# Rudder_-_Prototype_2.net
KiCad netlist of a schematic drawn in EAGLE
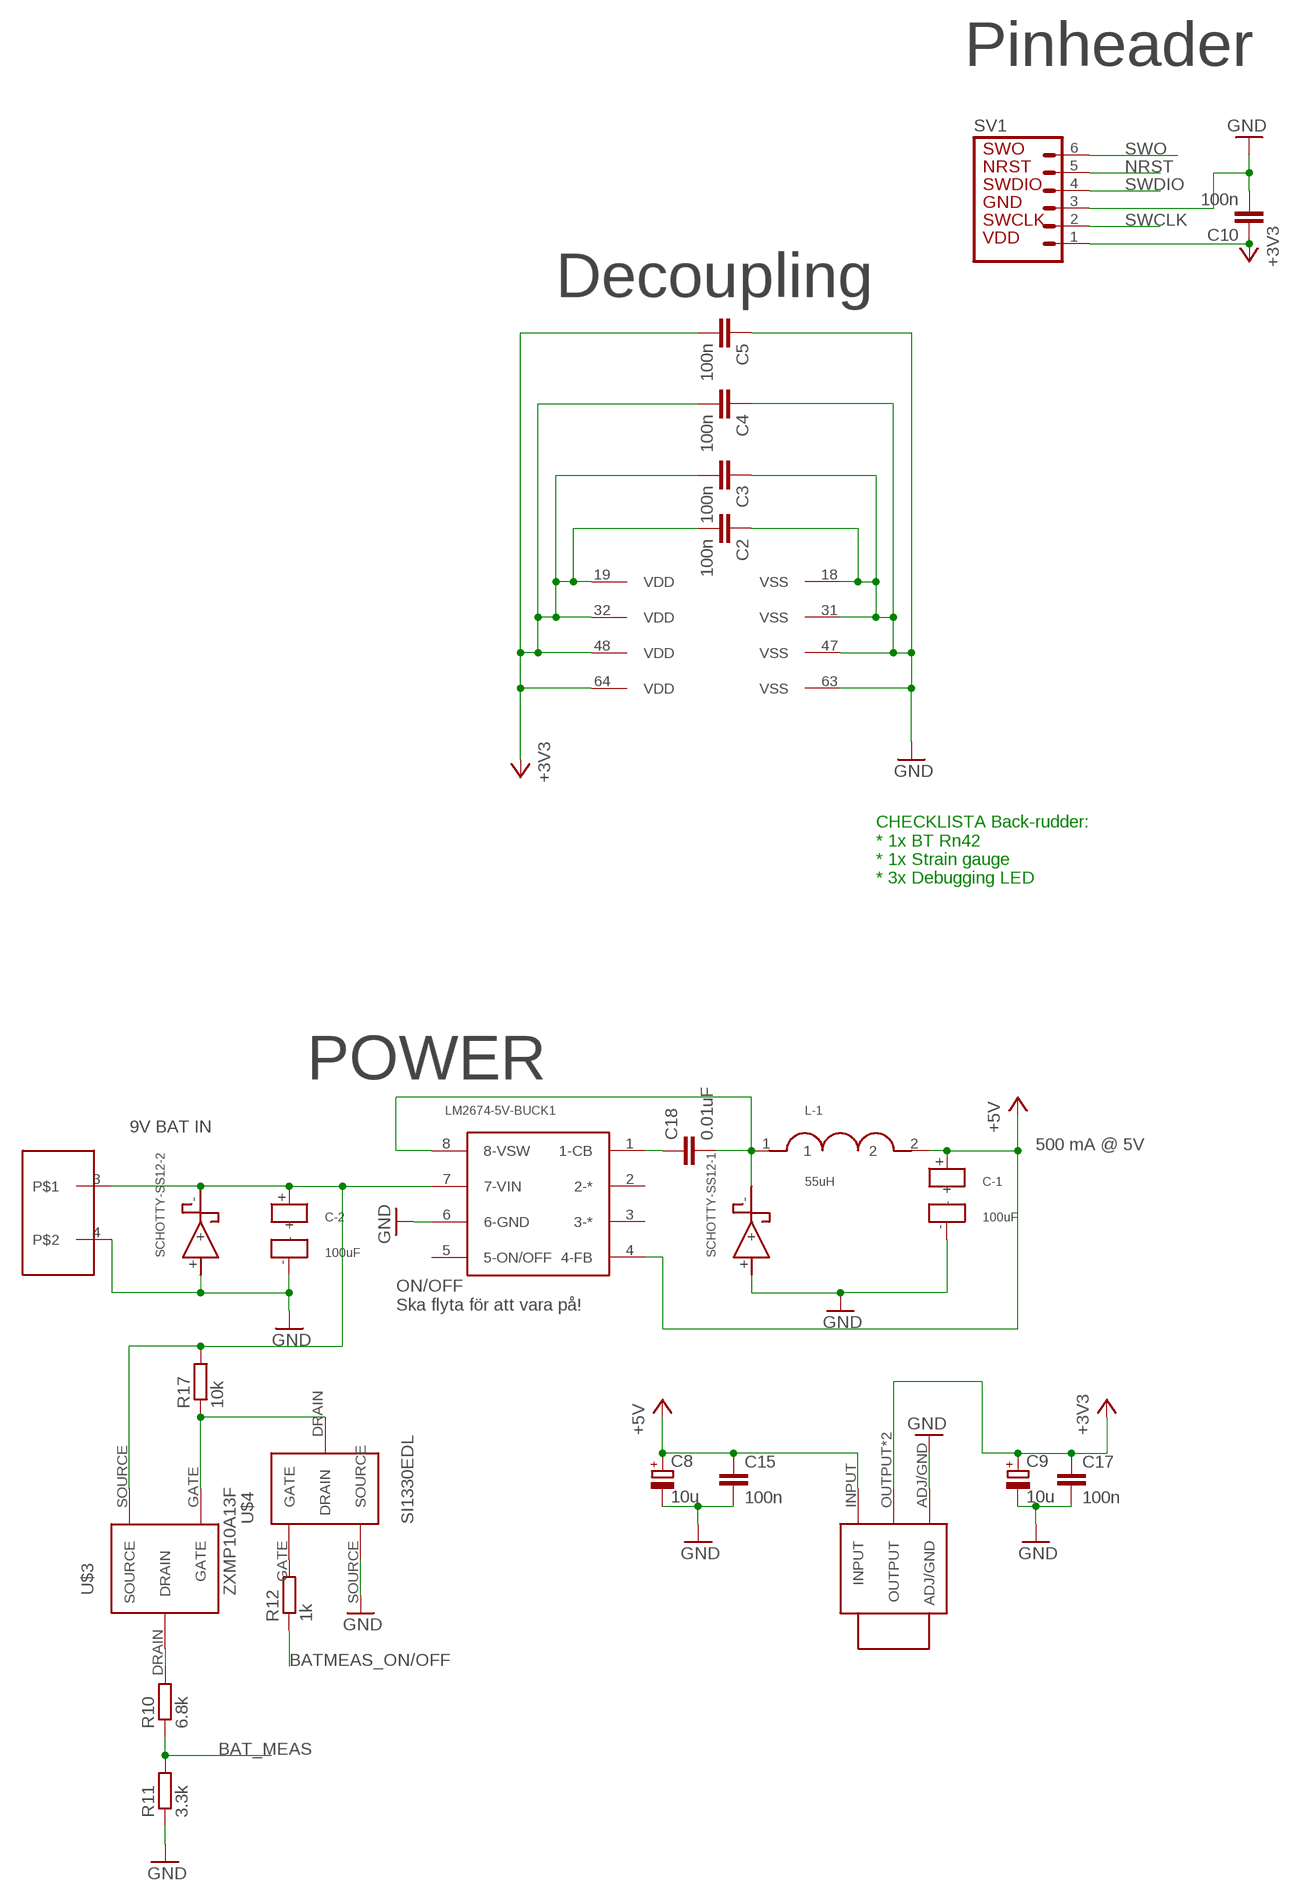
[diagram p0: schematic, sheet 1, part 1 of 2]
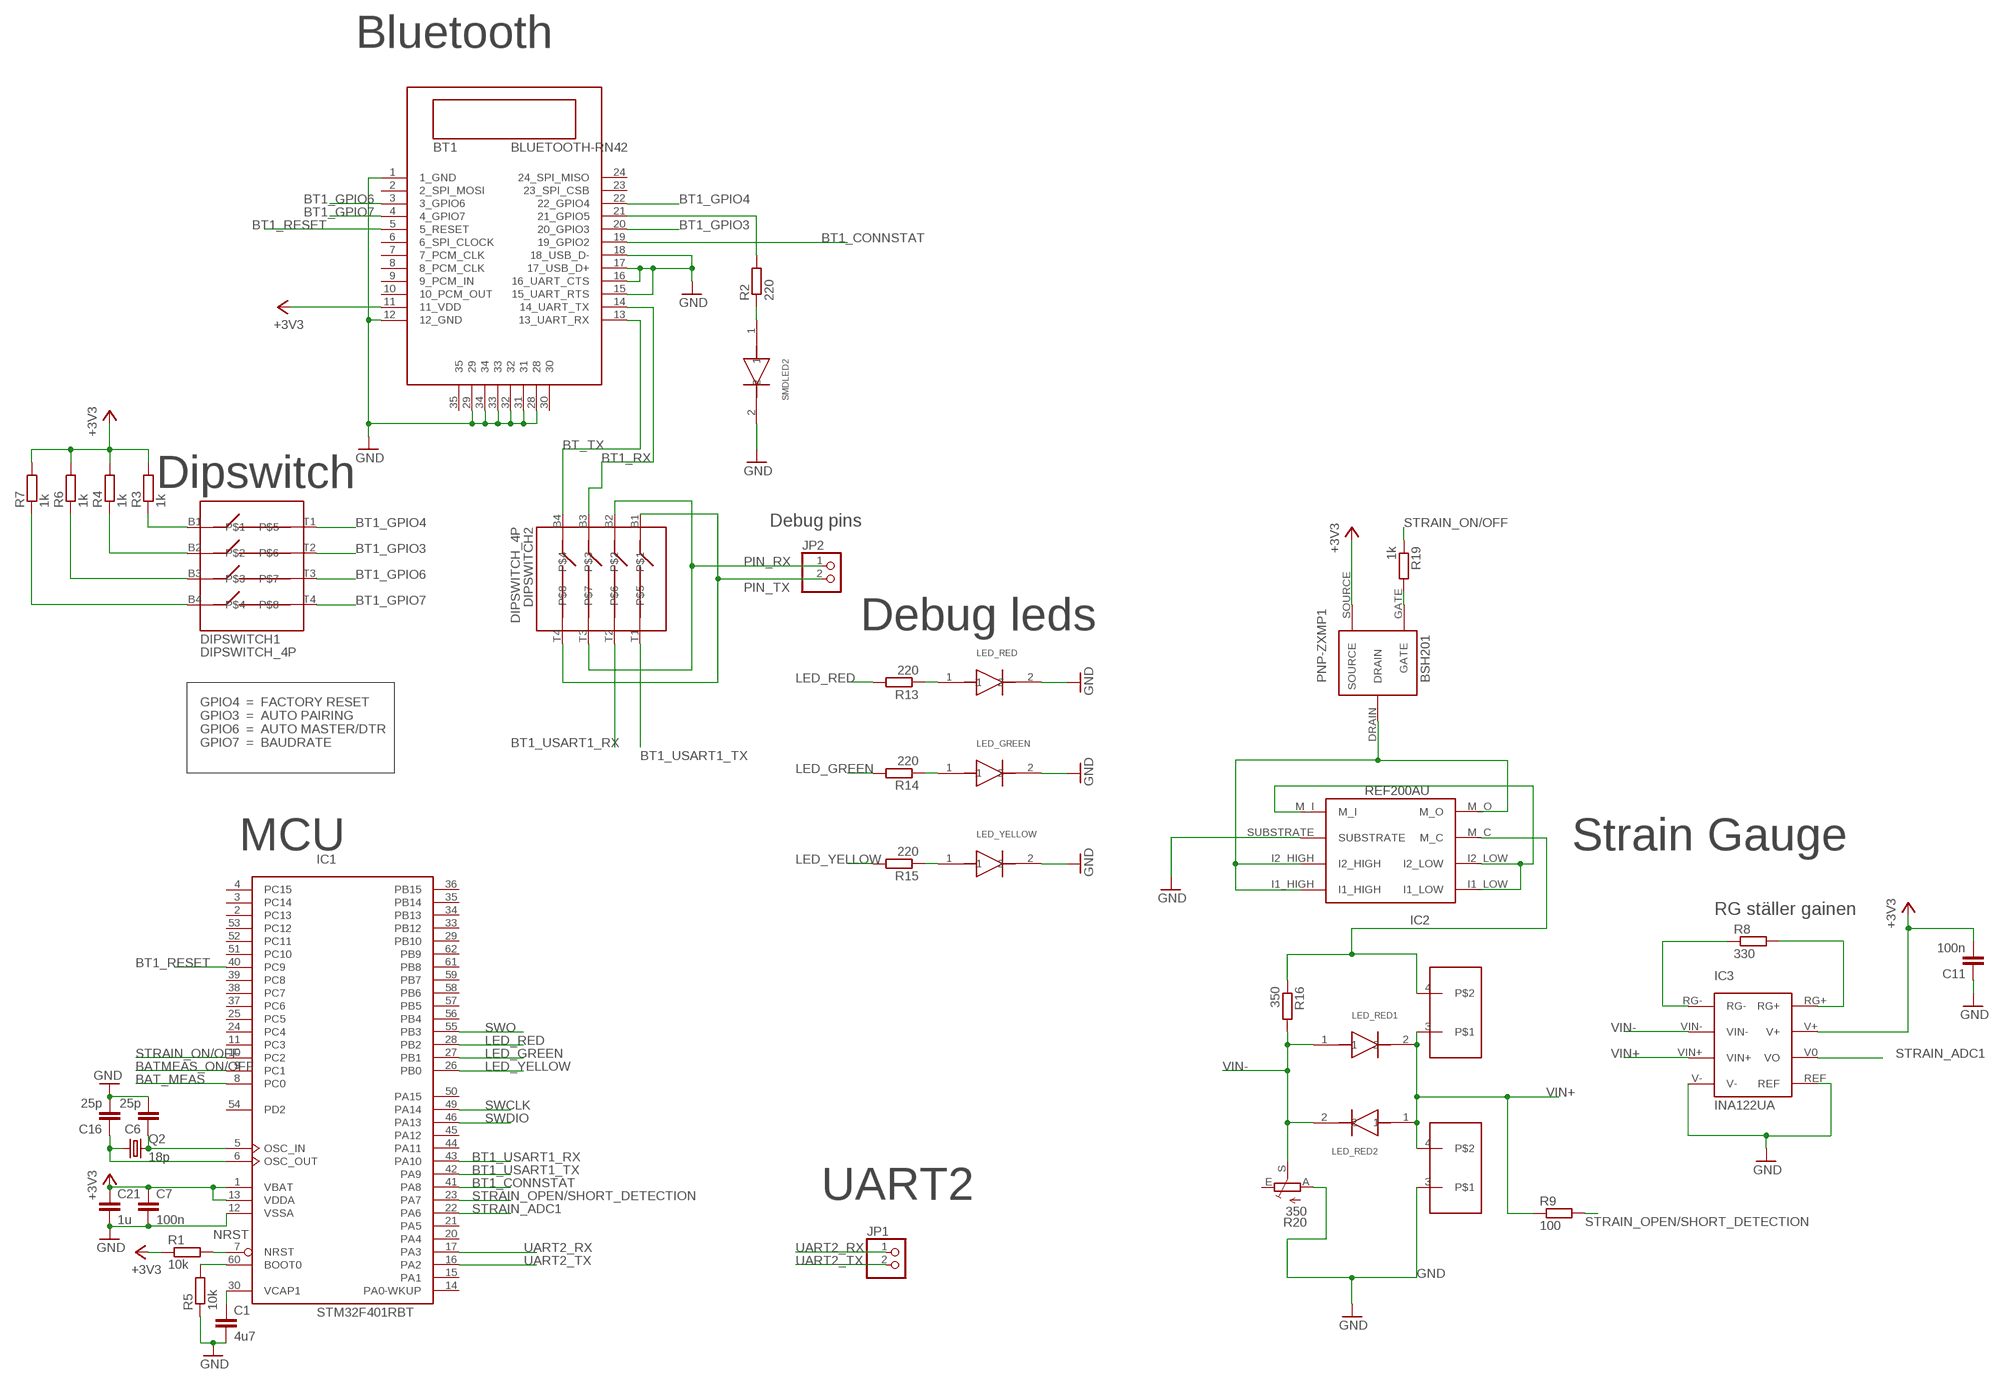
[diagram p1: schematic, sheet 1, part 2 of 2]

(export (version "E")
  (design (tool "Eeschema 10.0.6"))
  (components
    (comp (ref "BT1")
      (value "BLUETOOTH-RN42")
      (footprint "eagle-import:RN42")
      (libsource (lib "eagle-import") (part "BLUETOOTH-RN42"))
    )
    (comp (ref "C-1")
      (value "100uF")
      (footprint "eagle-import:CAP-6.3MM-DIA")
      (libsource (lib "eagle-import") (part "PANASONIC-CAP"))
    )
    (comp (ref "C-2")
      (value "100uF")
      (footprint "eagle-import:CAP-6.3MM-DIA")
      (libsource (lib "eagle-import") (part "PANASONIC-CAP"))
    )
    (comp (ref "C1")
      (value "4u7")
      (footprint "eagle-import:C0805")
      (libsource (lib "eagle-import") (part "C-EUC0805"))
    )
    (comp (ref "C2")
      (value "100n")
      (footprint "eagle-import:C0805")
      (libsource (lib "eagle-import") (part "C-EUC0805"))
    )
    (comp (ref "C3")
      (value "100n")
      (footprint "eagle-import:C0805")
      (libsource (lib "eagle-import") (part "C-EUC0805"))
    )
    (comp (ref "C4")
      (value "100n")
      (footprint "eagle-import:C0805")
      (libsource (lib "eagle-import") (part "C-EUC0805"))
    )
    (comp (ref "C5")
      (value "100n")
      (footprint "eagle-import:C0805")
      (libsource (lib "eagle-import") (part "C-EUC0805"))
    )
    (comp (ref "C6")
      (value "25p")
      (footprint "eagle-import:C0805")
      (libsource (lib "eagle-import") (part "C-EUC0805"))
    )
    (comp (ref "C7")
      (value "100n")
      (footprint "eagle-import:C0805")
      (libsource (lib "eagle-import") (part "C-EUC0805"))
    )
    (comp (ref "C8")
      (value "10u")
      (footprint "eagle-import:153CLV-0505")
      (libsource (lib "eagle-import") (part "CPOL-EU153CLV-0505"))
    )
    (comp (ref "C9")
      (value "10u")
      (footprint "eagle-import:153CLV-0505")
      (libsource (lib "eagle-import") (part "CPOL-EU153CLV-0505"))
    )
    (comp (ref "C10")
      (value "100n")
      (footprint "eagle-import:C0805")
      (libsource (lib "eagle-import") (part "C-EUC0805"))
    )
    (comp (ref "C11")
      (value "100n")
      (footprint "eagle-import:C0805")
      (libsource (lib "eagle-import") (part "C-EUC0805"))
    )
    (comp (ref "C15")
      (value "100n")
      (footprint "eagle-import:C0805")
      (libsource (lib "eagle-import") (part "C-EUC0805"))
    )
    (comp (ref "C16")
      (value "25p")
      (footprint "eagle-import:C0805")
      (libsource (lib "eagle-import") (part "C-EUC0805"))
    )
    (comp (ref "C17")
      (value "100n")
      (footprint "eagle-import:C0805")
      (libsource (lib "eagle-import") (part "C-EUC0805"))
    )
    (comp (ref "C18")
      (value "0.01uF")
      (footprint "eagle-import:C0805")
      (libsource (lib "eagle-import") (part "C-EUC0805"))
    )
    (comp (ref "C21")
      (value "1u")
      (footprint "eagle-import:C0805")
      (libsource (lib "eagle-import") (part "C-EUC0805"))
    )
    (comp (ref "DIPSWITCH1")
      (value "DIPSWITCH_4P")
      (footprint "eagle-import:DIPSWITCH4P")
      (libsource (lib "eagle-import") (part "DIPSWITCH_4P"))
    )
    (comp (ref "DIPSWITCH2")
      (value "DIPSWITCH_4P")
      (footprint "eagle-import:DIPSWITCH4P")
      (libsource (lib "eagle-import") (part "DIPSWITCH_4P"))
    )
    (comp (ref "IC1")
      (value "STM32F401RBT")
      (footprint "eagle-import:LQFP64")
      (libsource (lib "eagle-import") (part "STM32F401RTB"))
    )
    (comp (ref "IC2")
      (value "REF200AU")
      (footprint "eagle-import:SOIC(8)")
      (libsource (lib "eagle-import") (part "REF200AU"))
    )
    (comp (ref "IC3")
      (value "INA122UA")
      (footprint "eagle-import:S0-8")
      (libsource (lib "eagle-import") (part "INA122UA"))
    )
    (comp (ref "JP1")
      (value "PINHD-1X2")
      (footprint "eagle-import:1X02")
      (libsource (lib "eagle-import") (part "PINHD-1X2"))
    )
    (comp (ref "JP2")
      (value "PINHD-1X2")
      (footprint "eagle-import:1X02")
      (libsource (lib "eagle-import") (part "PINHD-1X2"))
    )
    (comp (ref "L-1")
      (value "55uH")
      (footprint "eagle-import:INDUCTOR")
      (libsource (lib "eagle-import") (part "55UH-INDUKTOR"))
    )
    (comp (ref "LED_GREEN")
      (value "SMD_LED")
      (footprint "eagle-import:SMD_LED_CUSTOM")
      (libsource (lib "eagle-import") (part "SMD_LED"))
    )
    (comp (ref "LED_RED")
      (value "SMD_LED")
      (footprint "eagle-import:SMD_LED_CUSTOM")
      (libsource (lib "eagle-import") (part "SMD_LED"))
    )
    (comp (ref "LED_RED1")
      (value "SMD_LED")
      (footprint "eagle-import:SMD_LED_CUSTOM")
      (libsource (lib "eagle-import") (part "SMD_LED"))
    )
    (comp (ref "LED_RED2")
      (value "SMD_LED")
      (footprint "eagle-import:SMD_LED_CUSTOM")
      (libsource (lib "eagle-import") (part "SMD_LED"))
    )
    (comp (ref "LED_YELLOW")
      (value "SMD_LED")
      (footprint "eagle-import:SMD_LED_CUSTOM")
      (libsource (lib "eagle-import") (part "SMD_LED"))
    )
    (comp (ref "LM1117-1")
      (value "LM1117")
      (footprint "eagle-import:LM1117")
      (libsource (lib "eagle-import") (part "LM1117"))
    )
    (comp (ref "LM2674-5V-BUCK1")
      (value "LM2674-5VBUCK")
      (footprint "eagle-import:LM2674")
      (libsource (lib "eagle-import") (part "LM2674-5VBUCK"))
    )
    (comp (ref "PNP-ZXMP1")
      (value "BSH201")
      (footprint "eagle-import:P-CHANNEL")
      (libsource (lib "eagle-import") (part "BSH201"))
    )
    (comp (ref "Q2")
      (value "18p")
      (footprint "eagle-import:HC49UP")
      (libsource (lib "eagle-import") (part "CRYSTALHC49UP"))
    )
    (comp (ref "R1")
      (value "10k")
      (footprint "eagle-import:R0805")
      (libsource (lib "eagle-import") (part "R-EU_R0805"))
    )
    (comp (ref "R2")
      (value "220")
      (footprint "eagle-import:R0805")
      (libsource (lib "eagle-import") (part "resistor_R-EU_R0805"))
    )
    (comp (ref "R3")
      (value "1k")
      (footprint "eagle-import:R0805")
      (libsource (lib "eagle-import") (part "resistor_R-EU_R0805"))
    )
    (comp (ref "R4")
      (value "1k")
      (footprint "eagle-import:R0805")
      (libsource (lib "eagle-import") (part "resistor_R-EU_R0805"))
    )
    (comp (ref "R5")
      (value "10k")
      (footprint "eagle-import:R0805")
      (libsource (lib "eagle-import") (part "R-EU_R0805"))
    )
    (comp (ref "R6")
      (value "1k")
      (footprint "eagle-import:R0805")
      (libsource (lib "eagle-import") (part "resistor_R-EU_R0805"))
    )
    (comp (ref "R7")
      (value "1k")
      (footprint "eagle-import:R0805")
      (libsource (lib "eagle-import") (part "resistor_R-EU_R0805"))
    )
    (comp (ref "R8")
      (value "330")
      (footprint "eagle-import:R0805")
      (libsource (lib "eagle-import") (part "R-EU_R0805"))
    )
    (comp (ref "R9")
      (value "100")
      (footprint "eagle-import:R0805")
      (libsource (lib "eagle-import") (part "R-EU_R0805"))
    )
    (comp (ref "R10")
      (value "6.8k")
      (footprint "eagle-import:R0805")
      (libsource (lib "eagle-import") (part "R-EU_R0805"))
    )
    (comp (ref "R11")
      (value "3.3k")
      (footprint "eagle-import:R0805")
      (libsource (lib "eagle-import") (part "R-EU_R0805"))
    )
    (comp (ref "R12")
      (value "1k")
      (footprint "eagle-import:R0805")
      (libsource (lib "eagle-import") (part "R-EU_R0805"))
    )
    (comp (ref "R13")
      (value "220")
      (footprint "eagle-import:R0805")
      (libsource (lib "eagle-import") (part "resistor_R-EU_R0805"))
    )
    (comp (ref "R14")
      (value "220")
      (footprint "eagle-import:R0805")
      (libsource (lib "eagle-import") (part "resistor_R-EU_R0805"))
    )
    (comp (ref "R15")
      (value "220")
      (footprint "eagle-import:R0805")
      (libsource (lib "eagle-import") (part "resistor_R-EU_R0805"))
    )
    (comp (ref "R16")
      (value "350")
      (footprint "eagle-import:R0805")
      (libsource (lib "eagle-import") (part "R-EU_R0805"))
    )
    (comp (ref "R17")
      (value "10k")
      (footprint "eagle-import:R0805")
      (libsource (lib "eagle-import") (part "R-EU_R0805"))
    )
    (comp (ref "R19")
      (value "1k")
      (footprint "eagle-import:R0805")
      (libsource (lib "eagle-import") (part "R-EU_R0805"))
    )
    (comp (ref "R20")
      (value "350")
      (footprint "eagle-import:S64W")
      (libsource (lib "eagle-import") (part "TRIM_EU-S64W"))
    )
    (comp (ref "SCHOTTY-SS12-1")
      (value "SCHOTTY-SS12")
      (footprint "eagle-import:SCHOTTY")
      (libsource (lib "eagle-import") (part "SCHOTTY-SS12"))
    )
    (comp (ref "SCHOTTY-SS12-2")
      (value "SCHOTTY-SS12")
      (footprint "eagle-import:SCHOTTY")
      (libsource (lib "eagle-import") (part "SCHOTTY-SS12"))
    )
    (comp (ref "SKRUVPLINT_2P1")
      (value "SKRUVPLINT_2P")
      (footprint "eagle-import:SKRUVPLINT_2P")
      (libsource (lib "eagle-import") (part "SKRUVPLINT_2P"))
    )
    (comp (ref "SKRUVPLINT_2P2")
      (value "SKRUVPLINT_2P")
      (footprint "eagle-import:SKRUVPLINT_2P")
      (libsource (lib "eagle-import") (part "SKRUVPLINT_2P"))
    )
    (comp (ref "SKRUVPLINT_2P3")
      (value "SKRUVPLINT_2P")
      (footprint "eagle-import:SKRUVPLINT_2P")
      (libsource (lib "eagle-import") (part "SKRUVPLINT_2P"))
    )
    (comp (ref "SMDLED2")
      (value "SMD_LED")
      (footprint "eagle-import:SMD_LED_CUSTOM")
      (libsource (lib "eagle-import") (part "SMD_LED"))
    )
    (comp (ref "SV1")
      (value "MA06-1")
      (footprint "eagle-import:MA06-1")
      (libsource (lib "eagle-import") (part "MA06-1"))
    )
    (comp (ref "U$3")
      (value "ZXMP10A13F")
      (footprint "eagle-import:P-CHANNEL")
      (libsource (lib "eagle-import") (part "ZXMP10A13F"))
    )
    (comp (ref "U$4")
      (value "SI1330EDL")
      (footprint "eagle-import:SOT-323")
      (libsource (lib "eagle-import") (part "SI1330EDL"))
    )
  )
  (nets
    (net (code "1") (name "+3V3") (class "Default")
      (node (ref "BT1") (pin "11") (pinfunction "11_VDD_11") (pintype "bidirectional"))
      (node (ref "C10") (pin "1") (pinfunction "1_1") (pintype "passive"))
      (node (ref "C11") (pin "2") (pinfunction "2_2") (pintype "passive"))
      (node (ref "C17") (pin "1") (pinfunction "1_1") (pintype "passive"))
      (node (ref "C2") (pin "2") (pinfunction "2_2") (pintype "passive"))
      (node (ref "C21") (pin "1") (pinfunction "1_1") (pintype "passive"))
      (node (ref "C3") (pin "2") (pinfunction "2_2") (pintype "passive"))
      (node (ref "C4") (pin "2") (pinfunction "2_2") (pintype "passive"))
      (node (ref "C5") (pin "2") (pinfunction "2_2") (pintype "passive"))
      (node (ref "C7") (pin "1") (pinfunction "1_1") (pintype "passive"))
      (node (ref "C9") (pin "+") (pinfunction "+_+") (pintype "passive"))
      (node (ref "IC1") (pin "1") (pinfunction "VBAT_1") (pintype "power_in"))
      (node (ref "IC1") (pin "13") (pinfunction "VDDA_13") (pintype "power_in"))
      (node (ref "IC1") (pin "19") (pinfunction "VDD_19") (pintype "power_in"))
      (node (ref "IC1") (pin "32") (pinfunction "VDD_32") (pintype "power_in"))
      (node (ref "IC1") (pin "48") (pinfunction "VDD_48") (pintype "power_in"))
      (node (ref "IC1") (pin "64") (pinfunction "VDD_64") (pintype "power_in"))
      (node (ref "IC3") (pin "V+") (pinfunction "V+_V+") (pintype "bidirectional"))
      (node (ref "LM1117-1") (pin "OUTPUT") (pinfunction "OUTPUT_OUTPUT") (pintype "bidirectional"))
      (node (ref "LM1117-1") (pin "OUTPUT2") (pinfunction "OUTPUT_OUTPUT2") (pintype "bidirectional"))
      (node (ref "PNP-ZXMP1") (pin "SOURCE") (pinfunction "SOURCE_SOURCE") (pintype "bidirectional"))
      (node (ref "R1") (pin "1") (pinfunction "1_1") (pintype "passive"))
      (node (ref "R3") (pin "2") (pinfunction "2_2") (pintype "passive"))
      (node (ref "R4") (pin "2") (pinfunction "2_2") (pintype "passive"))
      (node (ref "R6") (pin "2") (pinfunction "2_2") (pintype "passive"))
      (node (ref "R7") (pin "2") (pinfunction "2_2") (pintype "passive"))
      (node (ref "SV1") (pin "1") (pinfunction "1_1") (pintype "passive"))
    )
    (net (code "2") (name "+5V") (class "Default")
      (node (ref "C-1") (pin "+") (pinfunction "+_+") (pintype "bidirectional"))
      (node (ref "C15") (pin "1") (pinfunction "1_1") (pintype "passive"))
      (node (ref "C8") (pin "+") (pinfunction "+_+") (pintype "passive"))
      (node (ref "L-1") (pin "2") (pinfunction "2_2") (pintype "bidirectional"))
      (node (ref "LM1117-1") (pin "INPUT") (pinfunction "INPUT_INPUT") (pintype "bidirectional"))
      (node (ref "LM2674-5V-BUCK1") (pin "4") (pinfunction "4-FB_4") (pintype "bidirectional"))
    )
    (net (code "3") (name "/BATMEAS_ON{slash}OFF") (class "Default")
      (node (ref "IC1") (pin "9") (pinfunction "PC1_9") (pintype "bidirectional"))
      (node (ref "R12") (pin "1") (pinfunction "1_1") (pintype "passive"))
    )
    (net (code "4") (name "/BAT_MEAS") (class "Default")
      (node (ref "IC1") (pin "8") (pinfunction "PC0_8") (pintype "bidirectional"))
      (node (ref "R10") (pin "1") (pinfunction "1_1") (pintype "passive"))
      (node (ref "R11") (pin "2") (pinfunction "2_2") (pintype "passive"))
    )
    (net (code "5") (name "/BT1_CONNSTAT") (class "Default")
      (node (ref "BT1") (pin "19") (pinfunction "19_GPIO2_19") (pintype "bidirectional"))
      (node (ref "IC1") (pin "41") (pinfunction "PA8_41") (pintype "bidirectional"))
    )
    (net (code "6") (name "/BT1_GPIO3") (class "Default")
      (node (ref "BT1") (pin "20") (pinfunction "20_GPIO3_20") (pintype "bidirectional"))
      (node (ref "DIPSWITCH1") (pin "T2") (pinfunction "P$6_T2") (pintype "bidirectional"))
    )
    (net (code "7") (name "/BT1_GPIO4") (class "Default")
      (node (ref "BT1") (pin "22") (pinfunction "22_GPIO4_22") (pintype "bidirectional"))
      (node (ref "DIPSWITCH1") (pin "T1") (pinfunction "P$5_T1") (pintype "bidirectional"))
    )
    (net (code "8") (name "/BT1_GPIO6") (class "Default")
      (node (ref "BT1") (pin "3") (pinfunction "3_GPIO6_3") (pintype "bidirectional"))
      (node (ref "DIPSWITCH1") (pin "T3") (pinfunction "P$7_T3") (pintype "bidirectional"))
    )
    (net (code "9") (name "/BT1_GPIO7") (class "Default")
      (node (ref "BT1") (pin "4") (pinfunction "4_GPIO7_4") (pintype "bidirectional"))
      (node (ref "DIPSWITCH1") (pin "T4") (pinfunction "P$8_T4") (pintype "bidirectional"))
    )
    (net (code "10") (name "/BT1_RESET") (class "Default")
      (node (ref "BT1") (pin "5") (pinfunction "5_RESET_5") (pintype "bidirectional"))
      (node (ref "IC1") (pin "40") (pinfunction "PC9_40") (pintype "bidirectional"))
    )
    (net (code "11") (name "/BT1_RX") (class "Default")
      (node (ref "BT1") (pin "14") (pinfunction "14_UART_TX_14") (pintype "bidirectional"))
      (node (ref "DIPSWITCH2") (pin "B3") (pinfunction "P$3_B3") (pintype "bidirectional"))
    )
    (net (code "12") (name "/BT1_USART1_RX") (class "Default")
      (node (ref "DIPSWITCH2") (pin "T2") (pinfunction "P$6_T2") (pintype "bidirectional"))
      (node (ref "IC1") (pin "43") (pinfunction "PA10_43") (pintype "bidirectional"))
    )
    (net (code "13") (name "/BT1_USART1_TX") (class "Default")
      (node (ref "DIPSWITCH2") (pin "T1") (pinfunction "P$5_T1") (pintype "bidirectional"))
      (node (ref "IC1") (pin "42") (pinfunction "PA9_42") (pintype "bidirectional"))
    )
    (net (code "14") (name "/BT_TX") (class "Default")
      (node (ref "BT1") (pin "13") (pinfunction "13_UART_RX_13") (pintype "bidirectional"))
      (node (ref "DIPSWITCH2") (pin "B4") (pinfunction "P$4_B4") (pintype "bidirectional"))
    )
    (net (code "15") (name "/LED_GREEN") (class "Default")
      (node (ref "IC1") (pin "27") (pinfunction "PB1_27") (pintype "bidirectional"))
      (node (ref "R14") (pin "2") (pinfunction "2_2") (pintype "passive"))
    )
    (net (code "16") (name "/LED_RED") (class "Default")
      (node (ref "IC1") (pin "28") (pinfunction "PB2_28") (pintype "bidirectional"))
      (node (ref "R13") (pin "2") (pinfunction "2_2") (pintype "passive"))
    )
    (net (code "17") (name "/LED_YELLOW") (class "Default")
      (node (ref "IC1") (pin "26") (pinfunction "PB0_26") (pintype "bidirectional"))
      (node (ref "R15") (pin "2") (pinfunction "2_2") (pintype "passive"))
    )
    (net (code "18") (name "/NRST") (class "Default")
      (node (ref "IC1") (pin "7") (pinfunction "NRST_7") (pintype "bidirectional"))
      (node (ref "R1") (pin "2") (pinfunction "2_2") (pintype "passive"))
      (node (ref "SV1") (pin "5") (pinfunction "5_5") (pintype "passive"))
    )
    (net (code "19") (name "/PIN_RX") (class "Default")
      (node (ref "DIPSWITCH2") (pin "B2") (pinfunction "P$2_B2") (pintype "bidirectional"))
      (node (ref "DIPSWITCH2") (pin "T3") (pinfunction "P$7_T3") (pintype "bidirectional"))
      (node (ref "JP2") (pin "1") (pinfunction "1_1") (pintype "passive"))
    )
    (net (code "20") (name "/PIN_TX") (class "Default")
      (node (ref "DIPSWITCH2") (pin "B1") (pinfunction "P$1_B1") (pintype "bidirectional"))
      (node (ref "DIPSWITCH2") (pin "T4") (pinfunction "P$8_T4") (pintype "bidirectional"))
      (node (ref "JP2") (pin "2") (pinfunction "2_2") (pintype "passive"))
    )
    (net (code "21") (name "/STRAIN_ADC1") (class "Default")
      (node (ref "IC1") (pin "22") (pinfunction "PA6_22") (pintype "bidirectional"))
      (node (ref "IC3") (pin "V0") (pinfunction "VO_V0") (pintype "bidirectional"))
    )
    (net (code "22") (name "/STRAIN_ON{slash}OFF") (class "Default")
      (node (ref "IC1") (pin "10") (pinfunction "PC2_10") (pintype "bidirectional"))
      (node (ref "R19") (pin "1") (pinfunction "1_1") (pintype "passive"))
    )
    (net (code "23") (name "/STRAIN_OPEN{slash}SHORT_DETECTION") (class "Default")
      (node (ref "IC1") (pin "23") (pinfunction "PA7_23") (pintype "bidirectional"))
      (node (ref "R9") (pin "2") (pinfunction "2_2") (pintype "passive"))
    )
    (net (code "24") (name "/SWCLK") (class "Default")
      (node (ref "IC1") (pin "49") (pinfunction "PA14_49") (pintype "bidirectional"))
      (node (ref "SV1") (pin "2") (pinfunction "2_2") (pintype "passive"))
    )
    (net (code "25") (name "/SWDIO") (class "Default")
      (node (ref "IC1") (pin "46") (pinfunction "PA13_46") (pintype "bidirectional"))
      (node (ref "SV1") (pin "4") (pinfunction "4_4") (pintype "passive"))
    )
    (net (code "26") (name "/SWO") (class "Default")
      (node (ref "IC1") (pin "55") (pinfunction "PB3_55") (pintype "bidirectional"))
      (node (ref "SV1") (pin "6") (pinfunction "6_6") (pintype "passive"))
    )
    (net (code "27") (name "/UART2_RX") (class "Default")
      (node (ref "IC1") (pin "17") (pinfunction "PA3_17") (pintype "bidirectional"))
      (node (ref "JP1") (pin "1") (pinfunction "1_1") (pintype "passive"))
    )
    (net (code "28") (name "/UART2_TX") (class "Default")
      (node (ref "IC1") (pin "16") (pinfunction "PA2_16") (pintype "bidirectional"))
      (node (ref "JP1") (pin "2") (pinfunction "2_2") (pintype "passive"))
    )
    (net (code "29") (name "/VIN+") (class "Default")
      (node (ref "IC3") (pin "VIN+") (pinfunction "VIN+_VIN+") (pintype "bidirectional"))
      (node (ref "LED_RED1") (pin "2") (pinfunction "2_2") (pintype "bidirectional"))
      (node (ref "LED_RED2") (pin "1") (pinfunction "1_1") (pintype "bidirectional"))
      (node (ref "R9") (pin "1") (pinfunction "1_1") (pintype "passive"))
      (node (ref "SKRUVPLINT_2P1") (pin "3") (pinfunction "P$1_3") (pintype "bidirectional"))
      (node (ref "SKRUVPLINT_2P3") (pin "4") (pinfunction "P$2_4") (pintype "bidirectional"))
    )
    (net (code "30") (name "/VIN-") (class "Default")
      (node (ref "IC3") (pin "VIN-") (pinfunction "VIN-_VIN-") (pintype "bidirectional"))
      (node (ref "LED_RED1") (pin "1") (pinfunction "1_1") (pintype "bidirectional"))
      (node (ref "LED_RED2") (pin "2") (pinfunction "2_2") (pintype "bidirectional"))
      (node (ref "R16") (pin "2") (pinfunction "2_2") (pintype "passive"))
      (node (ref "R20") (pin "S") (pinfunction "S_S") (pintype "passive"))
    )
    (net (code "31") (name "GND") (class "Default")
      (node (ref "BT1") (pin "1") (pinfunction "1_GND_1") (pintype "bidirectional"))
      (node (ref "BT1") (pin "12") (pinfunction "12_GND_12") (pintype "bidirectional"))
      (node (ref "BT1") (pin "15") (pinfunction "15_UART_RTS_15") (pintype "bidirectional"))
      (node (ref "BT1") (pin "16") (pinfunction "16_UART_CTS_16") (pintype "bidirectional"))
      (node (ref "BT1") (pin "17") (pinfunction "17_USB_D+_17") (pintype "bidirectional"))
      (node (ref "BT1") (pin "18") (pinfunction "18_USB_D-_18") (pintype "bidirectional"))
      (node (ref "BT1") (pin "28") (pinfunction "28_28") (pintype "bidirectional"))
      (node (ref "BT1") (pin "29") (pinfunction "29_29") (pintype "bidirectional"))
      (node (ref "BT1") (pin "31") (pinfunction "31_31") (pintype "bidirectional"))
      (node (ref "BT1") (pin "32") (pinfunction "32_32") (pintype "bidirectional"))
      (node (ref "BT1") (pin "33") (pinfunction "33_33") (pintype "bidirectional"))
      (node (ref "BT1") (pin "34") (pinfunction "34_34") (pintype "bidirectional"))
      (node (ref "C-1") (pin "-") (pinfunction "-_-") (pintype "bidirectional"))
      (node (ref "C-2") (pin "-") (pinfunction "-_-") (pintype "bidirectional"))
      (node (ref "C1") (pin "2") (pinfunction "2_2") (pintype "passive"))
      (node (ref "C10") (pin "2") (pinfunction "2_2") (pintype "passive"))
      (node (ref "C11") (pin "1") (pinfunction "1_1") (pintype "passive"))
      (node (ref "C15") (pin "2") (pinfunction "2_2") (pintype "passive"))
      (node (ref "C16") (pin "2") (pinfunction "2_2") (pintype "passive"))
      (node (ref "C17") (pin "2") (pinfunction "2_2") (pintype "passive"))
      (node (ref "C2") (pin "1") (pinfunction "1_1") (pintype "passive"))
      (node (ref "C21") (pin "2") (pinfunction "2_2") (pintype "passive"))
      (node (ref "C3") (pin "1") (pinfunction "1_1") (pintype "passive"))
      (node (ref "C4") (pin "1") (pinfunction "1_1") (pintype "passive"))
      (node (ref "C5") (pin "1") (pinfunction "1_1") (pintype "passive"))
      (node (ref "C6") (pin "2") (pinfunction "2_2") (pintype "passive"))
      (node (ref "C7") (pin "2") (pinfunction "2_2") (pintype "passive"))
      (node (ref "C8") (pin "-") (pinfunction "-_-") (pintype "passive"))
      (node (ref "C9") (pin "-") (pinfunction "-_-") (pintype "passive"))
      (node (ref "IC1") (pin "12") (pinfunction "VSSA_12") (pintype "power_in"))
      (node (ref "IC1") (pin "18") (pinfunction "VSS_18") (pintype "power_in"))
      (node (ref "IC1") (pin "31") (pinfunction "VSS_31") (pintype "power_in"))
      (node (ref "IC1") (pin "47") (pinfunction "VSS_47") (pintype "power_in"))
      (node (ref "IC1") (pin "63") (pinfunction "VSS_63") (pintype "power_in"))
      (node (ref "IC2") (pin "SUBSTRATE") (pinfunction "SUBSTRATE_SUBSTRATE") (pintype "bidirectional"))
      (node (ref "IC3") (pin "REF") (pinfunction "REF_REF") (pintype "bidirectional"))
      (node (ref "IC3") (pin "V-") (pinfunction "V-_V-") (pintype "bidirectional"))
      (node (ref "LED_GREEN") (pin "2") (pinfunction "2_2") (pintype "bidirectional"))
      (node (ref "LED_RED") (pin "2") (pinfunction "2_2") (pintype "bidirectional"))
      (node (ref "LED_YELLOW") (pin "2") (pinfunction "2_2") (pintype "bidirectional"))
      (node (ref "LM1117-1") (pin "ADJ/GND") (pinfunction "ADJ/GND_ADJ/GND") (pintype "bidirectional"))
      (node (ref "LM2674-5V-BUCK1") (pin "6") (pinfunction "6-GND_6") (pintype "bidirectional"))
      (node (ref "R11") (pin "1") (pinfunction "1_1") (pintype "passive"))
      (node (ref "R20") (pin "A") (pinfunction "A_A") (pintype "passive"))
      (node (ref "R5") (pin "1") (pinfunction "1_1") (pintype "passive"))
      (node (ref "SCHOTTY-SS12-1") (pin "+") (pinfunction "+_+") (pintype "bidirectional"))
      (node (ref "SCHOTTY-SS12-2") (pin "+") (pinfunction "+_+") (pintype "bidirectional"))
      (node (ref "SKRUVPLINT_2P2") (pin "4") (pinfunction "P$2_4") (pintype "bidirectional"))
      (node (ref "SKRUVPLINT_2P3") (pin "3") (pinfunction "P$1_3") (pintype "bidirectional"))
      (node (ref "SMDLED2") (pin "2") (pinfunction "2_2") (pintype "bidirectional"))
      (node (ref "SV1") (pin "3") (pinfunction "3_3") (pintype "passive"))
      (node (ref "U$4") (pin "SOURCE") (pinfunction "SOURCE_SOURCE") (pintype "bidirectional"))
    )
    (net (code "32") (name "Net-(BT1-21_GPIO5)") (class "Default")
      (node (ref "BT1") (pin "21") (pinfunction "21_GPIO5_21") (pintype "bidirectional"))
      (node (ref "R2") (pin "2") (pinfunction "2_2") (pintype "passive"))
    )
    (net (code "33") (name "Net-(DIPSWITCH1-P$1)") (class "Default")
      (node (ref "DIPSWITCH1") (pin "B1") (pinfunction "P$1_B1") (pintype "bidirectional"))
      (node (ref "R3") (pin "1") (pinfunction "1_1") (pintype "passive"))
    )
    (net (code "34") (name "Net-(DIPSWITCH1-P$2)") (class "Default")
      (node (ref "DIPSWITCH1") (pin "B2") (pinfunction "P$2_B2") (pintype "bidirectional"))
      (node (ref "R4") (pin "1") (pinfunction "1_1") (pintype "passive"))
    )
    (net (code "35") (name "Net-(DIPSWITCH1-P$3)") (class "Default")
      (node (ref "DIPSWITCH1") (pin "B3") (pinfunction "P$3_B3") (pintype "bidirectional"))
      (node (ref "R6") (pin "1") (pinfunction "1_1") (pintype "passive"))
    )
    (net (code "36") (name "Net-(DIPSWITCH1-P$4)") (class "Default")
      (node (ref "DIPSWITCH1") (pin "B4") (pinfunction "P$4_B4") (pintype "bidirectional"))
      (node (ref "R7") (pin "1") (pinfunction "1_1") (pintype "passive"))
    )
    (net (code "37") (name "Net-(IC1A-BOOT0)") (class "Default")
      (node (ref "IC1") (pin "60") (pinfunction "BOOT0_60") (pintype "input"))
      (node (ref "R5") (pin "2") (pinfunction "2_2") (pintype "passive"))
    )
    (net (code "38") (name "Net-(IC1A-OSC_IN)") (class "Default")
      (node (ref "C6") (pin "1") (pinfunction "1_1") (pintype "passive"))
      (node (ref "IC1") (pin "5") (pinfunction "OSC_IN_5") (pintype "bidirectional"))
      (node (ref "Q2") (pin "2") (pinfunction "2_2") (pintype "passive"))
    )
    (net (code "39") (name "Net-(IC1A-OSC_OUT)") (class "Default")
      (node (ref "C16") (pin "1") (pinfunction "1_1") (pintype "passive"))
      (node (ref "IC1") (pin "6") (pinfunction "OSC_OUT_6") (pintype "bidirectional"))
      (node (ref "Q2") (pin "1") (pinfunction "1_1") (pintype "passive"))
    )
    (net (code "40") (name "Net-(IC1A-VCAP1)") (class "Default")
      (node (ref "C1") (pin "1") (pinfunction "1_1") (pintype "passive"))
      (node (ref "IC1") (pin "30") (pinfunction "VCAP1_30") (pintype "power_in"))
    )
    (net (code "41") (name "Net-(IC2-PadI1_HIGH)") (class "Default")
      (node (ref "IC2") (pin "I1_HIGH") (pinfunction "I1_HIGH_I1_HIGH") (pintype "bidirectional"))
      (node (ref "IC2") (pin "I2_HIGH") (pinfunction "I2_HIGH_I2_HIGH") (pintype "bidirectional"))
      (node (ref "IC2") (pin "M_O") (pinfunction "M_O_M_O") (pintype "bidirectional"))
      (node (ref "PNP-ZXMP1") (pin "DRAIN") (pinfunction "DRAIN_DRAIN") (pintype "bidirectional"))
    )
    (net (code "42") (name "Net-(IC2-PadI1_LOW)") (class "Default")
      (node (ref "IC2") (pin "I1_LOW") (pinfunction "I1_LOW_I1_LOW") (pintype "bidirectional"))
      (node (ref "IC2") (pin "I2_LOW") (pinfunction "I2_LOW_I2_LOW") (pintype "bidirectional"))
      (node (ref "IC2") (pin "M_I") (pinfunction "M_I_M_I") (pintype "bidirectional"))
    )
    (net (code "43") (name "Net-(IC3-PadRG+)") (class "Default")
      (node (ref "IC3") (pin "RG+") (pinfunction "RG+_RG+") (pintype "bidirectional"))
      (node (ref "R8") (pin "2") (pinfunction "2_2") (pintype "passive"))
    )
    (net (code "44") (name "Net-(IC3-PadRG-)") (class "Default")
      (node (ref "IC3") (pin "RG-") (pinfunction "RG-_RG-") (pintype "bidirectional"))
      (node (ref "R8") (pin "1") (pinfunction "1_1") (pintype "passive"))
    )
    (net (code "45") (name "Net-(LED_GREEN-Pad1)") (class "Default")
      (node (ref "LED_GREEN") (pin "1") (pinfunction "1_1") (pintype "bidirectional"))
      (node (ref "R14") (pin "1") (pinfunction "1_1") (pintype "passive"))
    )
    (net (code "46") (name "Net-(LED_RED-Pad1)") (class "Default")
      (node (ref "LED_RED") (pin "1") (pinfunction "1_1") (pintype "bidirectional"))
      (node (ref "R13") (pin "1") (pinfunction "1_1") (pintype "passive"))
    )
    (net (code "47") (name "Net-(LED_YELLOW-Pad1)") (class "Default")
      (node (ref "LED_YELLOW") (pin "1") (pinfunction "1_1") (pintype "bidirectional"))
      (node (ref "R15") (pin "1") (pinfunction "1_1") (pintype "passive"))
    )
    (net (code "48") (name "Net-(LM2674-5V-BUCK1-1-CB)") (class "Default")
      (node (ref "C18") (pin "1") (pinfunction "1_1") (pintype "passive"))
      (node (ref "LM2674-5V-BUCK1") (pin "1") (pinfunction "1-CB_1") (pintype "bidirectional"))
    )
    (net (code "49") (name "Net-(LM2674-5V-BUCK1-7-VIN)") (class "Default")
      (node (ref "C-2") (pin "+") (pinfunction "+_+") (pintype "bidirectional"))
      (node (ref "LM2674-5V-BUCK1") (pin "7") (pinfunction "7-VIN_7") (pintype "bidirectional"))
      (node (ref "R17") (pin "2") (pinfunction "2_2") (pintype "passive"))
      (node (ref "SCHOTTY-SS12-2") (pin "-") (pinfunction "-_-") (pintype "bidirectional"))
      (node (ref "SKRUVPLINT_2P2") (pin "3") (pinfunction "P$1_3") (pintype "bidirectional"))
      (node (ref "U$3") (pin "SOURCE") (pinfunction "SOURCE_SOURCE") (pintype "bidirectional"))
    )
    (net (code "50") (name "Net-(LM2674-5V-BUCK1-8-VSW)") (class "Default")
      (node (ref "C18") (pin "2") (pinfunction "2_2") (pintype "passive"))
      (node (ref "L-1") (pin "1") (pinfunction "1_1") (pintype "bidirectional"))
      (node (ref "LM2674-5V-BUCK1") (pin "8") (pinfunction "8-VSW_8") (pintype "bidirectional"))
      (node (ref "SCHOTTY-SS12-1") (pin "-") (pinfunction "-_-") (pintype "bidirectional"))
    )
    (net (code "51") (name "Net-(PNP-ZXMP1-PadGATE)") (class "Default")
      (node (ref "PNP-ZXMP1") (pin "GATE") (pinfunction "GATE_GATE") (pintype "bidirectional"))
      (node (ref "R19") (pin "2") (pinfunction "2_2") (pintype "passive"))
    )
    (net (code "52") (name "Net-(R2-Pad1)") (class "Default")
      (node (ref "R2") (pin "1") (pinfunction "1_1") (pintype "passive"))
      (node (ref "SMDLED2") (pin "1") (pinfunction "1_1") (pintype "bidirectional"))
    )
    (net (code "53") (name "Net-(R10-Pad2)") (class "Default")
      (node (ref "R10") (pin "2") (pinfunction "2_2") (pintype "passive"))
      (node (ref "U$3") (pin "DRAIN") (pinfunction "DRAIN_DRAIN") (pintype "bidirectional"))
    )
    (net (code "54") (name "Net-(R12-Pad2)") (class "Default")
      (node (ref "R12") (pin "2") (pinfunction "2_2") (pintype "passive"))
      (node (ref "U$4") (pin "GATE") (pinfunction "GATE_GATE") (pintype "bidirectional"))
    )
    (net (code "55") (name "Net-(R17-Pad1)") (class "Default")
      (node (ref "R17") (pin "1") (pinfunction "1_1") (pintype "passive"))
      (node (ref "U$3") (pin "GATE") (pinfunction "GATE_GATE") (pintype "bidirectional"))
      (node (ref "U$4") (pin "DRAIN") (pinfunction "DRAIN_DRAIN") (pintype "bidirectional"))
    )
    (net (code "56") (name "Net-(SKRUVPLINT_2P1-P$2)") (class "Default")
      (node (ref "IC2") (pin "M_C") (pinfunction "M_C_M_C") (pintype "bidirectional"))
      (node (ref "R16") (pin "1") (pinfunction "1_1") (pintype "passive"))
      (node (ref "SKRUVPLINT_2P1") (pin "4") (pinfunction "P$2_4") (pintype "bidirectional"))
    )
    (net (code "57") (name "unconnected-(BT1-2_SPI_MOSI-Pad2)") (class "Default")
      (node (ref "BT1") (pin "2") (pinfunction "2_SPI_MOSI_2") (pintype "bidirectional"))
    )
    (net (code "58") (name "unconnected-(BT1-6_SPI_CLOCK-Pad6)") (class "Default")
      (node (ref "BT1") (pin "6") (pinfunction "6_SPI_CLOCK_6") (pintype "bidirectional"))
    )
    (net (code "59") (name "unconnected-(BT1-7_PCM_CLK-Pad7)") (class "Default")
      (node (ref "BT1") (pin "7") (pinfunction "7_PCM_CLK_7") (pintype "bidirectional"))
    )
    (net (code "60") (name "unconnected-(BT1-8_PCM_CLK-Pad8)") (class "Default")
      (node (ref "BT1") (pin "8") (pinfunction "8_PCM_CLK_8") (pintype "bidirectional"))
    )
    (net (code "61") (name "unconnected-(BT1-9_PCM_IN-Pad9)") (class "Default")
      (node (ref "BT1") (pin "9") (pinfunction "9_PCM_IN_9") (pintype "bidirectional"))
    )
    (net (code "62") (name "unconnected-(BT1-10_PCM_OUT-Pad10)") (class "Default")
      (node (ref "BT1") (pin "10") (pinfunction "10_PCM_OUT_10") (pintype "bidirectional"))
    )
    (net (code "63") (name "unconnected-(BT1-23_SPI_CSB-Pad23)") (class "Default")
      (node (ref "BT1") (pin "23") (pinfunction "23_SPI_CSB_23") (pintype "bidirectional"))
    )
    (net (code "64") (name "unconnected-(BT1-24_SPI_MISO-Pad24)") (class "Default")
      (node (ref "BT1") (pin "24") (pinfunction "24_SPI_MISO_24") (pintype "bidirectional"))
    )
    (net (code "65") (name "unconnected-(BT1-Pad30)") (class "Default")
      (node (ref "BT1") (pin "30") (pinfunction "30_30") (pintype "bidirectional"))
    )
    (net (code "66") (name "unconnected-(BT1-Pad35)") (class "Default")
      (node (ref "BT1") (pin "35") (pinfunction "35_35") (pintype "bidirectional"))
    )
    (net (code "67") (name "unconnected-(IC1A-PA0-WKUP-Pad14)") (class "Default")
      (node (ref "IC1") (pin "14") (pinfunction "PA0-WKUP_14") (pintype "bidirectional"))
    )
    (net (code "68") (name "unconnected-(IC1A-PA1-Pad15)") (class "Default")
      (node (ref "IC1") (pin "15") (pinfunction "PA1_15") (pintype "bidirectional"))
    )
    (net (code "69") (name "unconnected-(IC1A-PA4-Pad20)") (class "Default")
      (node (ref "IC1") (pin "20") (pinfunction "PA4_20") (pintype "bidirectional"))
    )
    (net (code "70") (name "unconnected-(IC1A-PA5-Pad21)") (class "Default")
      (node (ref "IC1") (pin "21") (pinfunction "PA5_21") (pintype "bidirectional"))
    )
    (net (code "71") (name "unconnected-(IC1A-PA11-Pad44)") (class "Default")
      (node (ref "IC1") (pin "44") (pinfunction "PA11_44") (pintype "bidirectional"))
    )
    (net (code "72") (name "unconnected-(IC1A-PA12-Pad45)") (class "Default")
      (node (ref "IC1") (pin "45") (pinfunction "PA12_45") (pintype "bidirectional"))
    )
    (net (code "73") (name "unconnected-(IC1A-PA15-Pad50)") (class "Default")
      (node (ref "IC1") (pin "50") (pinfunction "PA15_50") (pintype "bidirectional"))
    )
    (net (code "74") (name "unconnected-(IC1A-PB4-Pad56)") (class "Default")
      (node (ref "IC1") (pin "56") (pinfunction "PB4_56") (pintype "bidirectional"))
    )
    (net (code "75") (name "unconnected-(IC1A-PB5-Pad57)") (class "Default")
      (node (ref "IC1") (pin "57") (pinfunction "PB5_57") (pintype "bidirectional"))
    )
    (net (code "76") (name "unconnected-(IC1A-PB6-Pad58)") (class "Default")
      (node (ref "IC1") (pin "58") (pinfunction "PB6_58") (pintype "bidirectional"))
    )
    (net (code "77") (name "unconnected-(IC1A-PB7-Pad59)") (class "Default")
      (node (ref "IC1") (pin "59") (pinfunction "PB7_59") (pintype "bidirectional"))
    )
    (net (code "78") (name "unconnected-(IC1A-PB8-Pad61)") (class "Default")
      (node (ref "IC1") (pin "61") (pinfunction "PB8_61") (pintype "bidirectional"))
    )
    (net (code "79") (name "unconnected-(IC1A-PB9-Pad62)") (class "Default")
      (node (ref "IC1") (pin "62") (pinfunction "PB9_62") (pintype "bidirectional"))
    )
    (net (code "80") (name "unconnected-(IC1A-PB10-Pad29)") (class "Default")
      (node (ref "IC1") (pin "29") (pinfunction "PB10_29") (pintype "bidirectional"))
    )
    (net (code "81") (name "unconnected-(IC1A-PB12-Pad33)") (class "Default")
      (node (ref "IC1") (pin "33") (pinfunction "PB12_33") (pintype "bidirectional"))
    )
    (net (code "82") (name "unconnected-(IC1A-PB13-Pad34)") (class "Default")
      (node (ref "IC1") (pin "34") (pinfunction "PB13_34") (pintype "bidirectional"))
    )
    (net (code "83") (name "unconnected-(IC1A-PB14-Pad35)") (class "Default")
      (node (ref "IC1") (pin "35") (pinfunction "PB14_35") (pintype "bidirectional"))
    )
    (net (code "84") (name "unconnected-(IC1A-PB15-Pad36)") (class "Default")
      (node (ref "IC1") (pin "36") (pinfunction "PB15_36") (pintype "bidirectional"))
    )
    (net (code "85") (name "unconnected-(IC1A-PC3-Pad11)") (class "Default")
      (node (ref "IC1") (pin "11") (pinfunction "PC3_11") (pintype "bidirectional"))
    )
    (net (code "86") (name "unconnected-(IC1A-PC4-Pad24)") (class "Default")
      (node (ref "IC1") (pin "24") (pinfunction "PC4_24") (pintype "bidirectional"))
    )
    (net (code "87") (name "unconnected-(IC1A-PC5-Pad25)") (class "Default")
      (node (ref "IC1") (pin "25") (pinfunction "PC5_25") (pintype "bidirectional"))
    )
    (net (code "88") (name "unconnected-(IC1A-PC6-Pad37)") (class "Default")
      (node (ref "IC1") (pin "37") (pinfunction "PC6_37") (pintype "bidirectional"))
    )
    (net (code "89") (name "unconnected-(IC1A-PC7-Pad38)") (class "Default")
      (node (ref "IC1") (pin "38") (pinfunction "PC7_38") (pintype "bidirectional"))
    )
    (net (code "90") (name "unconnected-(IC1A-PC8-Pad39)") (class "Default")
      (node (ref "IC1") (pin "39") (pinfunction "PC8_39") (pintype "bidirectional"))
    )
    (net (code "91") (name "unconnected-(IC1A-PC10-Pad51)") (class "Default")
      (node (ref "IC1") (pin "51") (pinfunction "PC10_51") (pintype "bidirectional"))
    )
    (net (code "92") (name "unconnected-(IC1A-PC11-Pad52)") (class "Default")
      (node (ref "IC1") (pin "52") (pinfunction "PC11_52") (pintype "bidirectional"))
    )
    (net (code "93") (name "unconnected-(IC1A-PC12-Pad53)") (class "Default")
      (node (ref "IC1") (pin "53") (pinfunction "PC12_53") (pintype "bidirectional"))
    )
    (net (code "94") (name "unconnected-(IC1A-PC13-Pad2)") (class "Default")
      (node (ref "IC1") (pin "2") (pinfunction "PC13_2") (pintype "bidirectional"))
    )
    (net (code "95") (name "unconnected-(IC1A-PC14-Pad3)") (class "Default")
      (node (ref "IC1") (pin "3") (pinfunction "PC14_3") (pintype "bidirectional"))
    )
    (net (code "96") (name "unconnected-(IC1A-PC15-Pad4)") (class "Default")
      (node (ref "IC1") (pin "4") (pinfunction "PC15_4") (pintype "bidirectional"))
    )
    (net (code "97") (name "unconnected-(IC1A-PD2-Pad54)") (class "Default")
      (node (ref "IC1") (pin "54") (pinfunction "PD2_54") (pintype "bidirectional"))
    )
    (net (code "98") (name "unconnected-(LM2674-5V-BUCK1-2-*-Pad2)") (class "Default")
      (node (ref "LM2674-5V-BUCK1") (pin "2") (pinfunction "2-*_2") (pintype "bidirectional"))
    )
    (net (code "99") (name "unconnected-(LM2674-5V-BUCK1-3-*-Pad3)") (class "Default")
      (node (ref "LM2674-5V-BUCK1") (pin "3") (pinfunction "3-*_3") (pintype "bidirectional"))
    )
    (net (code "100") (name "unconnected-(LM2674-5V-BUCK1-5-ON{slash}OFF-Pad5)") (class "Default")
      (node (ref "LM2674-5V-BUCK1") (pin "5") (pinfunction "5-ON/OFF_5") (pintype "bidirectional"))
    )
    (net (code "101") (name "unconnected-(R20-PadE)") (class "Default")
      (node (ref "R20") (pin "E") (pinfunction "E_E") (pintype "passive"))
    )
  )
)
